# CONDITIONING.net
KiCad netlist of a schematic drawn in Altium Designer
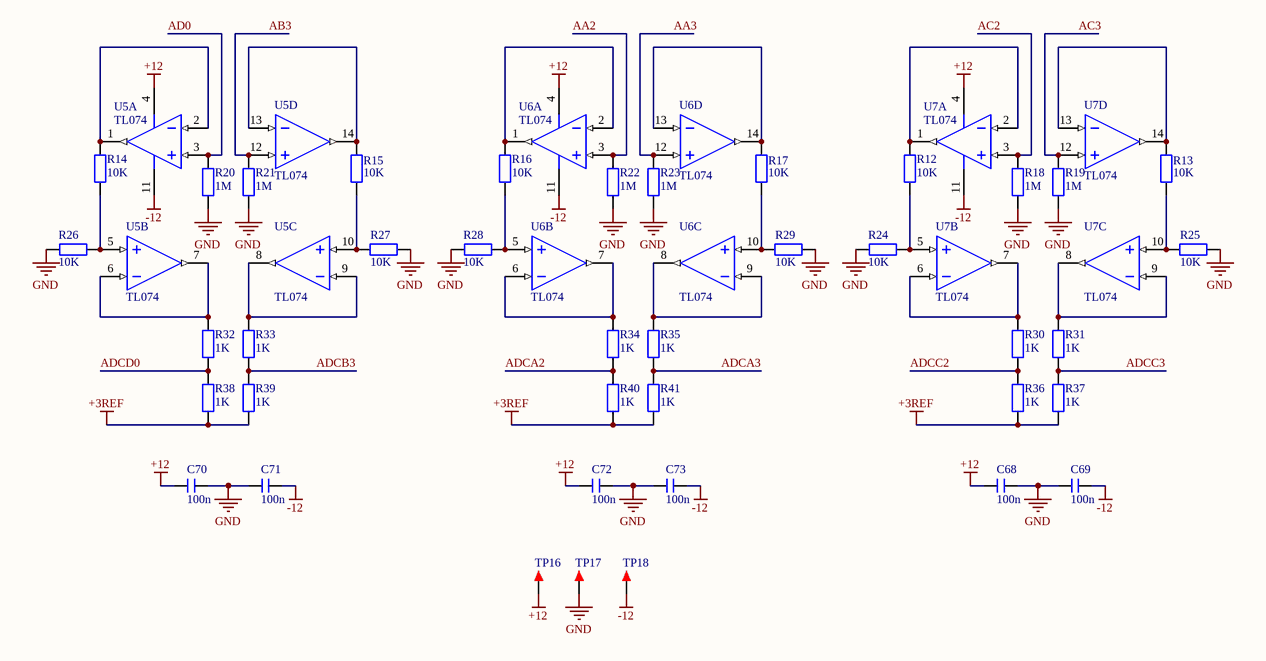
[diagram p0: CONDITIONING.SchDoc]

(export (version "E")
  (design (tool "Eeschema 10.0.6"))
  (components
    (comp (ref "C68")
      (value "100n")
      (footprint "C 0805_L")
      (description "贴片电容")
      (libsource (lib "01 - 电容-电阻-电感") (part "C"))
    )
    (comp (ref "C69")
      (value "100n")
      (footprint "C 0805_L")
      (description "贴片电容")
      (libsource (lib "01 - 电容-电阻-电感") (part "C"))
    )
    (comp (ref "C70")
      (value "100n")
      (footprint "C 0805_L")
      (description "贴片电容")
      (libsource (lib "01 - 电容-电阻-电感") (part "C"))
    )
    (comp (ref "C71")
      (value "100n")
      (footprint "C 0805_L")
      (description "贴片电容")
      (libsource (lib "01 - 电容-电阻-电感") (part "C"))
    )
    (comp (ref "C72")
      (value "100n")
      (footprint "C 0805_L")
      (description "贴片电容")
      (libsource (lib "01 - 电容-电阻-电感") (part "C"))
    )
    (comp (ref "C73")
      (value "100n")
      (footprint "C 0805_L")
      (description "贴片电容")
      (libsource (lib "01 - 电容-电阻-电感") (part "C"))
    )
    (comp (ref "R12")
      (value "10K")
      (footprint "R 0805_L")
      (description "贴片电阻")
      (libsource (lib "01 - 电容-电阻-电感") (part "R"))
    )
    (comp (ref "R13")
      (value "10K")
      (footprint "R 0805_L")
      (description "贴片电阻")
      (libsource (lib "01 - 电容-电阻-电感") (part "R"))
    )
    (comp (ref "R14")
      (value "10K")
      (footprint "R 0805_L")
      (description "贴片电阻")
      (libsource (lib "01 - 电容-电阻-电感") (part "R"))
    )
    (comp (ref "R15")
      (value "10K")
      (footprint "R 0805_L")
      (description "贴片电阻")
      (libsource (lib "01 - 电容-电阻-电感") (part "R"))
    )
    (comp (ref "R16")
      (value "10K")
      (footprint "R 0805_L")
      (description "贴片电阻")
      (libsource (lib "01 - 电容-电阻-电感") (part "R"))
    )
    (comp (ref "R17")
      (value "10K")
      (footprint "R 0805_L")
      (description "贴片电阻")
      (libsource (lib "01 - 电容-电阻-电感") (part "R"))
    )
    (comp (ref "R18")
      (value "1M")
      (footprint "R 0805_L")
      (description "贴片电阻")
      (libsource (lib "01 - 电容-电阻-电感") (part "R"))
    )
    (comp (ref "R19")
      (value "1M")
      (footprint "R 0805_L")
      (description "贴片电阻")
      (libsource (lib "01 - 电容-电阻-电感") (part "R"))
    )
    (comp (ref "R20")
      (value "1M")
      (footprint "R 0805_L")
      (description "贴片电阻")
      (libsource (lib "01 - 电容-电阻-电感") (part "R"))
    )
    (comp (ref "R21")
      (value "1M")
      (footprint "R 0805_L")
      (description "贴片电阻")
      (libsource (lib "01 - 电容-电阻-电感") (part "R"))
    )
    (comp (ref "R22")
      (value "1M")
      (footprint "R 0805_L")
      (description "贴片电阻")
      (libsource (lib "01 - 电容-电阻-电感") (part "R"))
    )
    (comp (ref "R23")
      (value "1M")
      (footprint "R 0805_L")
      (description "贴片电阻")
      (libsource (lib "01 - 电容-电阻-电感") (part "R"))
    )
    (comp (ref "R24")
      (value "10K")
      (footprint "R 0805_L")
      (description "贴片电阻")
      (libsource (lib "01 - 电容-电阻-电感") (part "R"))
    )
    (comp (ref "R25")
      (value "10K")
      (footprint "R 0805_L")
      (description "贴片电阻")
      (libsource (lib "01 - 电容-电阻-电感") (part "R"))
    )
    (comp (ref "R26")
      (value "10K")
      (footprint "R 0805_L")
      (description "贴片电阻")
      (libsource (lib "01 - 电容-电阻-电感") (part "R"))
    )
    (comp (ref "R27")
      (value "10K")
      (footprint "R 0805_L")
      (description "贴片电阻")
      (libsource (lib "01 - 电容-电阻-电感") (part "R"))
    )
    (comp (ref "R28")
      (value "10K")
      (footprint "R 0805_L")
      (description "贴片电阻")
      (libsource (lib "01 - 电容-电阻-电感") (part "R"))
    )
    (comp (ref "R29")
      (value "10K")
      (footprint "R 0805_L")
      (description "贴片电阻")
      (libsource (lib "01 - 电容-电阻-电感") (part "R"))
    )
    (comp (ref "R30")
      (value "1K")
      (footprint "R 0805_L")
      (description "贴片电阻")
      (libsource (lib "01 - 电容-电阻-电感") (part "R"))
    )
    (comp (ref "R31")
      (value "1K")
      (footprint "R 0805_L")
      (description "贴片电阻")
      (libsource (lib "01 - 电容-电阻-电感") (part "R"))
    )
    (comp (ref "R32")
      (value "1K")
      (footprint "R 0805_L")
      (description "贴片电阻")
      (libsource (lib "01 - 电容-电阻-电感") (part "R"))
    )
    (comp (ref "R33")
      (value "1K")
      (footprint "R 0805_L")
      (description "贴片电阻")
      (libsource (lib "01 - 电容-电阻-电感") (part "R"))
    )
    (comp (ref "R34")
      (value "1K")
      (footprint "R 0805_L")
      (description "贴片电阻")
      (libsource (lib "01 - 电容-电阻-电感") (part "R"))
    )
    (comp (ref "R35")
      (value "1K")
      (footprint "R 0805_L")
      (description "贴片电阻")
      (libsource (lib "01 - 电容-电阻-电感") (part "R"))
    )
    (comp (ref "R36")
      (value "1K")
      (footprint "R 0805_L")
      (description "贴片电阻")
      (libsource (lib "01 - 电容-电阻-电感") (part "R"))
    )
    (comp (ref "R37")
      (value "1K")
      (footprint "R 0805_L")
      (description "贴片电阻")
      (libsource (lib "01 - 电容-电阻-电感") (part "R"))
    )
    (comp (ref "R38")
      (value "1K")
      (footprint "R 0805_L")
      (description "贴片电阻")
      (libsource (lib "01 - 电容-电阻-电感") (part "R"))
    )
    (comp (ref "R39")
      (value "1K")
      (footprint "R 0805_L")
      (description "贴片电阻")
      (libsource (lib "01 - 电容-电阻-电感") (part "R"))
    )
    (comp (ref "R40")
      (value "1K")
      (footprint "R 0805_L")
      (description "贴片电阻")
      (libsource (lib "01 - 电容-电阻-电感") (part "R"))
    )
    (comp (ref "R41")
      (value "1K")
      (footprint "R 0805_L")
      (description "贴片电阻")
      (libsource (lib "01 - 电容-电阻-电感") (part "R"))
    )
    (comp (ref "TP16")
      (value "TEST")
      (footprint "TEST 1")
      (description "测试点")
      (libsource (lib "10 - 未分类元器件") (part "TEST"))
    )
    (comp (ref "TP17")
      (value "TEST")
      (footprint "TEST 1")
      (description "测试点")
      (libsource (lib "10 - 未分类元器件") (part "TEST"))
    )
    (comp (ref "TP18")
      (value "TEST")
      (footprint "TEST 1")
      (description "测试点")
      (libsource (lib "10 - 未分类元器件") (part "TEST"))
    )
    (comp (ref "U5")
      (value "TL074")
      (footprint "SOP14_N")
      (description "Low Noise JFET-Input Operational Amplifiers")
      (libsource (lib "12 - 比较器") (part "TL074"))
    )
    (comp (ref "U6")
      (value "TL074")
      (footprint "SOP14_N")
      (description "Low Noise JFET-Input Operational Amplifiers")
      (libsource (lib "12 - 比较器") (part "TL074"))
    )
    (comp (ref "U7")
      (value "TL074")
      (footprint "SOP14_N")
      (description "Low Noise JFET-Input Operational Amplifiers")
      (libsource (lib "12 - 比较器") (part "TL074"))
    )
  )
  (nets
    (net (code "1") (name "+3REF") (class "Default")
      (node (ref "R36") (pin "1") (pinfunction "1_1") (pintype "passive"))
      (node (ref "R37") (pin "1") (pinfunction "1_1") (pintype "passive"))
      (node (ref "R38") (pin "1") (pinfunction "1_1") (pintype "passive"))
      (node (ref "R39") (pin "1") (pinfunction "1_1") (pintype "passive"))
      (node (ref "R40") (pin "1") (pinfunction "1_1") (pintype "passive"))
      (node (ref "R41") (pin "1") (pinfunction "1_1") (pintype "passive"))
    )
    (net (code "2") (name "+12") (class "Default")
      (node (ref "C68") (pin "1") (pinfunction "1_1") (pintype "passive"))
      (node (ref "C70") (pin "1") (pinfunction "1_1") (pintype "passive"))
      (node (ref "C72") (pin "1") (pinfunction "1_1") (pintype "passive"))
      (node (ref "TP16") (pin "1") (pinfunction "1_1") (pintype "passive"))
      (node (ref "U5") (pin "4") (pinfunction "VCC+_4") (pintype "power_in"))
      (node (ref "U6") (pin "4") (pinfunction "VCC+_4") (pintype "power_in"))
      (node (ref "U7") (pin "4") (pinfunction "VCC+_4") (pintype "power_in"))
    )
    (net (code "3") (name "-12") (class "Default")
      (node (ref "C69") (pin "2") (pinfunction "2_2") (pintype "passive"))
      (node (ref "C71") (pin "2") (pinfunction "2_2") (pintype "passive"))
      (node (ref "C73") (pin "2") (pinfunction "2_2") (pintype "passive"))
      (node (ref "TP18") (pin "1") (pinfunction "1_1") (pintype "passive"))
      (node (ref "U5") (pin "11") (pinfunction "VCC-_11") (pintype "power_in"))
      (node (ref "U6") (pin "11") (pinfunction "VCC-_11") (pintype "power_in"))
      (node (ref "U7") (pin "11") (pinfunction "VCC-_11") (pintype "power_in"))
    )
    (net (code "4") (name "/AA2") (class "Default")
      (node (ref "R22") (pin "2") (pinfunction "2_2") (pintype "passive"))
      (node (ref "U6") (pin "3") (pinfunction "IN1+_3") (pintype "input"))
    )
    (net (code "5") (name "/AA3") (class "Default")
      (node (ref "R23") (pin "2") (pinfunction "2_2") (pintype "passive"))
      (node (ref "U6") (pin "12") (pinfunction "IN3+_12") (pintype "input"))
    )
    (net (code "6") (name "/AB3") (class "Default")
      (node (ref "R21") (pin "2") (pinfunction "2_2") (pintype "passive"))
      (node (ref "U5") (pin "12") (pinfunction "IN3+_12") (pintype "input"))
    )
    (net (code "7") (name "/AC2") (class "Default")
      (node (ref "R18") (pin "2") (pinfunction "2_2") (pintype "passive"))
      (node (ref "U7") (pin "3") (pinfunction "IN1+_3") (pintype "input"))
    )
    (net (code "8") (name "/AC3") (class "Default")
      (node (ref "R19") (pin "2") (pinfunction "2_2") (pintype "passive"))
      (node (ref "U7") (pin "12") (pinfunction "IN3+_12") (pintype "input"))
    )
    (net (code "9") (name "/AD0") (class "Default")
      (node (ref "R20") (pin "2") (pinfunction "2_2") (pintype "passive"))
      (node (ref "U5") (pin "3") (pinfunction "IN1+_3") (pintype "input"))
    )
    (net (code "10") (name "/ADCA2") (class "Default")
      (node (ref "R34") (pin "1") (pinfunction "1_1") (pintype "passive"))
      (node (ref "R40") (pin "2") (pinfunction "2_2") (pintype "passive"))
    )
    (net (code "11") (name "/ADCA3") (class "Default")
      (node (ref "R35") (pin "1") (pinfunction "1_1") (pintype "passive"))
      (node (ref "R41") (pin "2") (pinfunction "2_2") (pintype "passive"))
    )
    (net (code "12") (name "/ADCB3") (class "Default")
      (node (ref "R33") (pin "1") (pinfunction "1_1") (pintype "passive"))
      (node (ref "R39") (pin "2") (pinfunction "2_2") (pintype "passive"))
    )
    (net (code "13") (name "/ADCC2") (class "Default")
      (node (ref "R30") (pin "1") (pinfunction "1_1") (pintype "passive"))
      (node (ref "R36") (pin "2") (pinfunction "2_2") (pintype "passive"))
    )
    (net (code "14") (name "/ADCC3") (class "Default")
      (node (ref "R31") (pin "1") (pinfunction "1_1") (pintype "passive"))
      (node (ref "R37") (pin "2") (pinfunction "2_2") (pintype "passive"))
    )
    (net (code "15") (name "/ADCD0") (class "Default")
      (node (ref "R32") (pin "1") (pinfunction "1_1") (pintype "passive"))
      (node (ref "R38") (pin "2") (pinfunction "2_2") (pintype "passive"))
    )
    (net (code "16") (name "GND") (class "Default")
      (node (ref "C68") (pin "2") (pinfunction "2_2") (pintype "passive"))
      (node (ref "C69") (pin "1") (pinfunction "1_1") (pintype "passive"))
      (node (ref "C70") (pin "2") (pinfunction "2_2") (pintype "passive"))
      (node (ref "C71") (pin "1") (pinfunction "1_1") (pintype "passive"))
      (node (ref "C72") (pin "2") (pinfunction "2_2") (pintype "passive"))
      (node (ref "C73") (pin "1") (pinfunction "1_1") (pintype "passive"))
      (node (ref "R18") (pin "1") (pinfunction "1_1") (pintype "passive"))
      (node (ref "R19") (pin "1") (pinfunction "1_1") (pintype "passive"))
      (node (ref "R20") (pin "1") (pinfunction "1_1") (pintype "passive"))
      (node (ref "R21") (pin "1") (pinfunction "1_1") (pintype "passive"))
      (node (ref "R22") (pin "1") (pinfunction "1_1") (pintype "passive"))
      (node (ref "R23") (pin "1") (pinfunction "1_1") (pintype "passive"))
      (node (ref "R24") (pin "1") (pinfunction "1_1") (pintype "passive"))
      (node (ref "R25") (pin "1") (pinfunction "1_1") (pintype "passive"))
      (node (ref "R26") (pin "1") (pinfunction "1_1") (pintype "passive"))
      (node (ref "R27") (pin "1") (pinfunction "1_1") (pintype "passive"))
      (node (ref "R28") (pin "1") (pinfunction "1_1") (pintype "passive"))
      (node (ref "R29") (pin "1") (pinfunction "1_1") (pintype "passive"))
      (node (ref "TP17") (pin "1") (pinfunction "1_1") (pintype "passive"))
    )
    (net (code "17") (name "Net-(U5A-IN1-)") (class "Default")
      (node (ref "R14") (pin "2") (pinfunction "2_2") (pintype "passive"))
      (node (ref "U5") (pin "1") (pinfunction "OUT_1") (pintype "output"))
      (node (ref "U5") (pin "2") (pinfunction "IN1-_2") (pintype "input"))
    )
    (net (code "18") (name "Net-(U5B-IN2+)") (class "Default")
      (node (ref "R14") (pin "1") (pinfunction "1_1") (pintype "passive"))
      (node (ref "R26") (pin "2") (pinfunction "2_2") (pintype "passive"))
      (node (ref "U5") (pin "5") (pinfunction "IN2+_5") (pintype "input"))
    )
    (net (code "19") (name "Net-(U5B-IN2-)") (class "Default")
      (node (ref "R32") (pin "2") (pinfunction "2_2") (pintype "passive"))
      (node (ref "U5") (pin "6") (pinfunction "IN2-_6") (pintype "input"))
      (node (ref "U5") (pin "7") (pinfunction "OUT_7") (pintype "output"))
    )
    (net (code "20") (name "Net-(U5C-IN4+)") (class "Default")
      (node (ref "R15") (pin "1") (pinfunction "1_1") (pintype "passive"))
      (node (ref "R27") (pin "2") (pinfunction "2_2") (pintype "passive"))
      (node (ref "U5") (pin "10") (pinfunction "IN4+_10") (pintype "input"))
    )
    (net (code "21") (name "Net-(U5C-IN4-)") (class "Default")
      (node (ref "R33") (pin "2") (pinfunction "2_2") (pintype "passive"))
      (node (ref "U5") (pin "8") (pinfunction "OUT_8") (pintype "output"))
      (node (ref "U5") (pin "9") (pinfunction "IN4-_9") (pintype "input"))
    )
    (net (code "22") (name "Net-(U5D-IN3-)") (class "Default")
      (node (ref "R15") (pin "2") (pinfunction "2_2") (pintype "passive"))
      (node (ref "U5") (pin "13") (pinfunction "IN3-_13") (pintype "input"))
      (node (ref "U5") (pin "14") (pinfunction "OUT_14") (pintype "output"))
    )
    (net (code "23") (name "Net-(U6A-IN1-)") (class "Default")
      (node (ref "R16") (pin "2") (pinfunction "2_2") (pintype "passive"))
      (node (ref "U6") (pin "1") (pinfunction "OUT_1") (pintype "output"))
      (node (ref "U6") (pin "2") (pinfunction "IN1-_2") (pintype "input"))
    )
    (net (code "24") (name "Net-(U6B-IN2+)") (class "Default")
      (node (ref "R16") (pin "1") (pinfunction "1_1") (pintype "passive"))
      (node (ref "R28") (pin "2") (pinfunction "2_2") (pintype "passive"))
      (node (ref "U6") (pin "5") (pinfunction "IN2+_5") (pintype "input"))
    )
    (net (code "25") (name "Net-(U6B-IN2-)") (class "Default")
      (node (ref "R34") (pin "2") (pinfunction "2_2") (pintype "passive"))
      (node (ref "U6") (pin "6") (pinfunction "IN2-_6") (pintype "input"))
      (node (ref "U6") (pin "7") (pinfunction "OUT_7") (pintype "output"))
    )
    (net (code "26") (name "Net-(U6C-IN4+)") (class "Default")
      (node (ref "R17") (pin "1") (pinfunction "1_1") (pintype "passive"))
      (node (ref "R29") (pin "2") (pinfunction "2_2") (pintype "passive"))
      (node (ref "U6") (pin "10") (pinfunction "IN4+_10") (pintype "input"))
    )
    (net (code "27") (name "Net-(U6C-IN4-)") (class "Default")
      (node (ref "R35") (pin "2") (pinfunction "2_2") (pintype "passive"))
      (node (ref "U6") (pin "8") (pinfunction "OUT_8") (pintype "output"))
      (node (ref "U6") (pin "9") (pinfunction "IN4-_9") (pintype "input"))
    )
    (net (code "28") (name "Net-(U6D-IN3-)") (class "Default")
      (node (ref "R17") (pin "2") (pinfunction "2_2") (pintype "passive"))
      (node (ref "U6") (pin "13") (pinfunction "IN3-_13") (pintype "input"))
      (node (ref "U6") (pin "14") (pinfunction "OUT_14") (pintype "output"))
    )
    (net (code "29") (name "Net-(U7A-IN1-)") (class "Default")
      (node (ref "R12") (pin "2") (pinfunction "2_2") (pintype "passive"))
      (node (ref "U7") (pin "1") (pinfunction "OUT_1") (pintype "output"))
      (node (ref "U7") (pin "2") (pinfunction "IN1-_2") (pintype "input"))
    )
    (net (code "30") (name "Net-(U7B-IN2+)") (class "Default")
      (node (ref "R12") (pin "1") (pinfunction "1_1") (pintype "passive"))
      (node (ref "R24") (pin "2") (pinfunction "2_2") (pintype "passive"))
      (node (ref "U7") (pin "5") (pinfunction "IN2+_5") (pintype "input"))
    )
    (net (code "31") (name "Net-(U7B-IN2-)") (class "Default")
      (node (ref "R30") (pin "2") (pinfunction "2_2") (pintype "passive"))
      (node (ref "U7") (pin "6") (pinfunction "IN2-_6") (pintype "input"))
      (node (ref "U7") (pin "7") (pinfunction "OUT_7") (pintype "output"))
    )
    (net (code "32") (name "Net-(U7C-IN4+)") (class "Default")
      (node (ref "R13") (pin "1") (pinfunction "1_1") (pintype "passive"))
      (node (ref "R25") (pin "2") (pinfunction "2_2") (pintype "passive"))
      (node (ref "U7") (pin "10") (pinfunction "IN4+_10") (pintype "input"))
    )
    (net (code "33") (name "Net-(U7C-IN4-)") (class "Default")
      (node (ref "R31") (pin "2") (pinfunction "2_2") (pintype "passive"))
      (node (ref "U7") (pin "8") (pinfunction "OUT_8") (pintype "output"))
      (node (ref "U7") (pin "9") (pinfunction "IN4-_9") (pintype "input"))
    )
    (net (code "34") (name "Net-(U7D-IN3-)") (class "Default")
      (node (ref "R13") (pin "2") (pinfunction "2_2") (pintype "passive"))
      (node (ref "U7") (pin "13") (pinfunction "IN3-_13") (pintype "input"))
      (node (ref "U7") (pin "14") (pinfunction "OUT_14") (pintype "output"))
    )
  )
)
